# Interposer.net
KiCad netlist of a schematic drawn in EAGLE
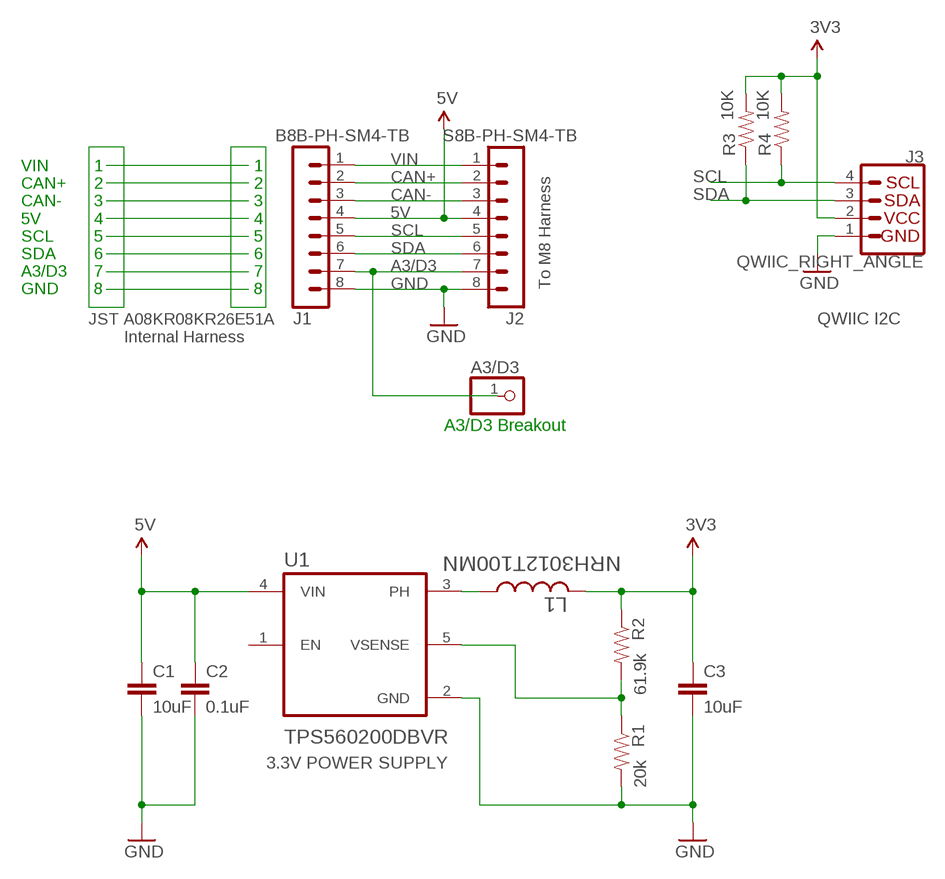
[diagram p0: schematic, sheet 1]

(export (version "E")
  (design (tool "Eeschema 10.0.6"))
  (components
    (comp (ref "A3/D3")
      (value "PINHD-1X1")
      (footprint "eagle-import:1X01")
      (libsource (lib "eagle-import") (part "PINHD-1X1"))
    )
    (comp (ref "C1")
      (value "10uF")
      (footprint "eagle-import:0603-CAP")
      (libsource (lib "eagle-import") (part "CAP-10UF-0603"))
    )
    (comp (ref "C2")
      (value "0.1uF")
      (footprint "eagle-import:0603-CAP")
      (libsource (lib "eagle-import") (part "CAP-10UF-0603"))
    )
    (comp (ref "C3")
      (value "10uF")
      (footprint "eagle-import:0603-CAP")
      (libsource (lib "eagle-import") (part "CAP-10UF-0603"))
    )
    (comp (ref "J1")
      (value "B8B-PH-SM4-TB")
      (footprint "eagle-import:B8B-PH-SM4-TB")
      (libsource (lib "eagle-import") (part "B8B-PH-SM4-TB"))
    )
    (comp (ref "J2")
      (value "S8B-PH-SM4-TB")
      (footprint "eagle-import:S8B-PH-SM4-TB")
      (libsource (lib "eagle-import") (part "S8B-PH-SM4-TB"))
    )
    (comp (ref "J3")
      (value "QWIIC_RIGHT_ANGLE")
      (footprint "eagle-import:JST04_1MM_RA")
      (libsource (lib "eagle-import") (part "QWIIC_CONNECTORJS-1MM"))
    )
    (comp (ref "L1")
      (value "NRH3012T100MN")
      (footprint "eagle-import:IND_TAIYO_NRH3012_TAY")
      (libsource (lib "eagle-import") (part "NRH3012T100MN"))
    )
    (comp (ref "R1")
      (value "20k")
      (footprint "eagle-import:0603-RES")
      (libsource (lib "eagle-import") (part "RES-10K-06030603"))
    )
    (comp (ref "R2")
      (value "61.9k")
      (footprint "eagle-import:0603-RES")
      (libsource (lib "eagle-import") (part "RES-10K-06030603"))
    )
    (comp (ref "R3")
      (value "10K")
      (footprint "eagle-import:0603-RES")
      (libsource (lib "eagle-import") (part "RES-10K-06030603"))
    )
    (comp (ref "R4")
      (value "10K")
      (footprint "eagle-import:0603-RES")
      (libsource (lib "eagle-import") (part "RES-10K-06030603"))
    )
    (comp (ref "U1")
      (value "TPS560200DBVR")
      (footprint "eagle-import:SOT95P280X145-5N")
      (fields (field (name "DIGI-KEY_PART_NUMBER") "296-38559-1-ND") (field (name "MF") "Texas Instruments"))
      (libsource (lib "eagle-import") (part "TPS560200DBVR"))
    )
  )
  (nets
    (net (code "1") (name "/A3{slash}D3") (class "Default")
      (node (ref "A3/D3") (pin "1") (pinfunction "1_1") (pintype "passive"))
      (node (ref "J1") (pin "7") (pinfunction "7_7") (pintype "passive"))
      (node (ref "J2") (pin "7") (pinfunction "7_7") (pintype "passive"))
    )
    (net (code "2") (name "/CAN+") (class "Default")
      (node (ref "J1") (pin "2") (pinfunction "2_2") (pintype "passive"))
      (node (ref "J2") (pin "2") (pinfunction "2_2") (pintype "passive"))
    )
    (net (code "3") (name "/CAN-") (class "Default")
      (node (ref "J1") (pin "3") (pinfunction "3_3") (pintype "passive"))
      (node (ref "J2") (pin "3") (pinfunction "3_3") (pintype "passive"))
    )
    (net (code "4") (name "/SCL") (class "Default")
      (node (ref "J1") (pin "5") (pinfunction "5_5") (pintype "passive"))
      (node (ref "J2") (pin "5") (pinfunction "5_5") (pintype "passive"))
      (node (ref "J3") (pin "4") (pinfunction "4_4") (pintype "passive"))
      (node (ref "R4") (pin "1") (pinfunction "1_1") (pintype "passive"))
    )
    (net (code "5") (name "/SDA") (class "Default")
      (node (ref "J1") (pin "6") (pinfunction "6_6") (pintype "passive"))
      (node (ref "J2") (pin "6") (pinfunction "6_6") (pintype "passive"))
      (node (ref "J3") (pin "3") (pinfunction "3_3") (pintype "passive"))
      (node (ref "R3") (pin "1") (pinfunction "1_1") (pintype "passive"))
    )
    (net (code "6") (name "/VIN") (class "Default")
      (node (ref "J1") (pin "1") (pinfunction "1_1") (pintype "passive"))
      (node (ref "J2") (pin "1") (pinfunction "1_1") (pintype "passive"))
    )
    (net (code "7") (name "3V3") (class "Default")
      (node (ref "C3") (pin "1") (pinfunction "1_1") (pintype "passive"))
      (node (ref "J3") (pin "2") (pinfunction "2_2") (pintype "power_in"))
      (node (ref "L1") (pin "2") (pinfunction "2_2") (pintype "passive"))
      (node (ref "R2") (pin "1") (pinfunction "1_1") (pintype "passive"))
      (node (ref "R3") (pin "2") (pinfunction "2_2") (pintype "passive"))
      (node (ref "R4") (pin "2") (pinfunction "2_2") (pintype "passive"))
    )
    (net (code "8") (name "5V") (class "Default")
      (node (ref "C1") (pin "1") (pinfunction "1_1") (pintype "passive"))
      (node (ref "C2") (pin "1") (pinfunction "1_1") (pintype "passive"))
      (node (ref "J1") (pin "4") (pinfunction "4_4") (pintype "passive"))
      (node (ref "J2") (pin "4") (pinfunction "4_4") (pintype "passive"))
      (node (ref "U1") (pin "4") (pinfunction "VIN_4") (pintype "power_in"))
    )
    (net (code "9") (name "GND") (class "Default")
      (node (ref "C1") (pin "2") (pinfunction "2_2") (pintype "passive"))
      (node (ref "C2") (pin "2") (pinfunction "2_2") (pintype "passive"))
      (node (ref "C3") (pin "2") (pinfunction "2_2") (pintype "passive"))
      (node (ref "J1") (pin "8") (pinfunction "8_8") (pintype "passive"))
      (node (ref "J2") (pin "8") (pinfunction "8_8") (pintype "passive"))
      (node (ref "J3") (pin "1") (pinfunction "1_1") (pintype "power_in"))
      (node (ref "R1") (pin "2") (pinfunction "2_2") (pintype "passive"))
      (node (ref "U1") (pin "2") (pinfunction "GND_2") (pintype "power_in"))
    )
    (net (code "10") (name "Net-(U1-PH)") (class "Default")
      (node (ref "L1") (pin "1") (pinfunction "1_1") (pintype "passive"))
      (node (ref "U1") (pin "3") (pinfunction "PH_3") (pintype "input"))
    )
    (net (code "11") (name "Net-(U1-VSENSE)") (class "Default")
      (node (ref "R1") (pin "1") (pinfunction "1_1") (pintype "passive"))
      (node (ref "R2") (pin "2") (pinfunction "2_2") (pintype "passive"))
      (node (ref "U1") (pin "5") (pinfunction "VSENSE_5") (pintype "bidirectional"))
    )
    (net (code "12") (name "unconnected-(U1-EN-Pad1)") (class "Default")
      (node (ref "U1") (pin "1") (pinfunction "EN_1") (pintype "input"))
    )
  )
)
